# boxer_main.net
KiCad netlist of a schematic drawn in Altium Designer
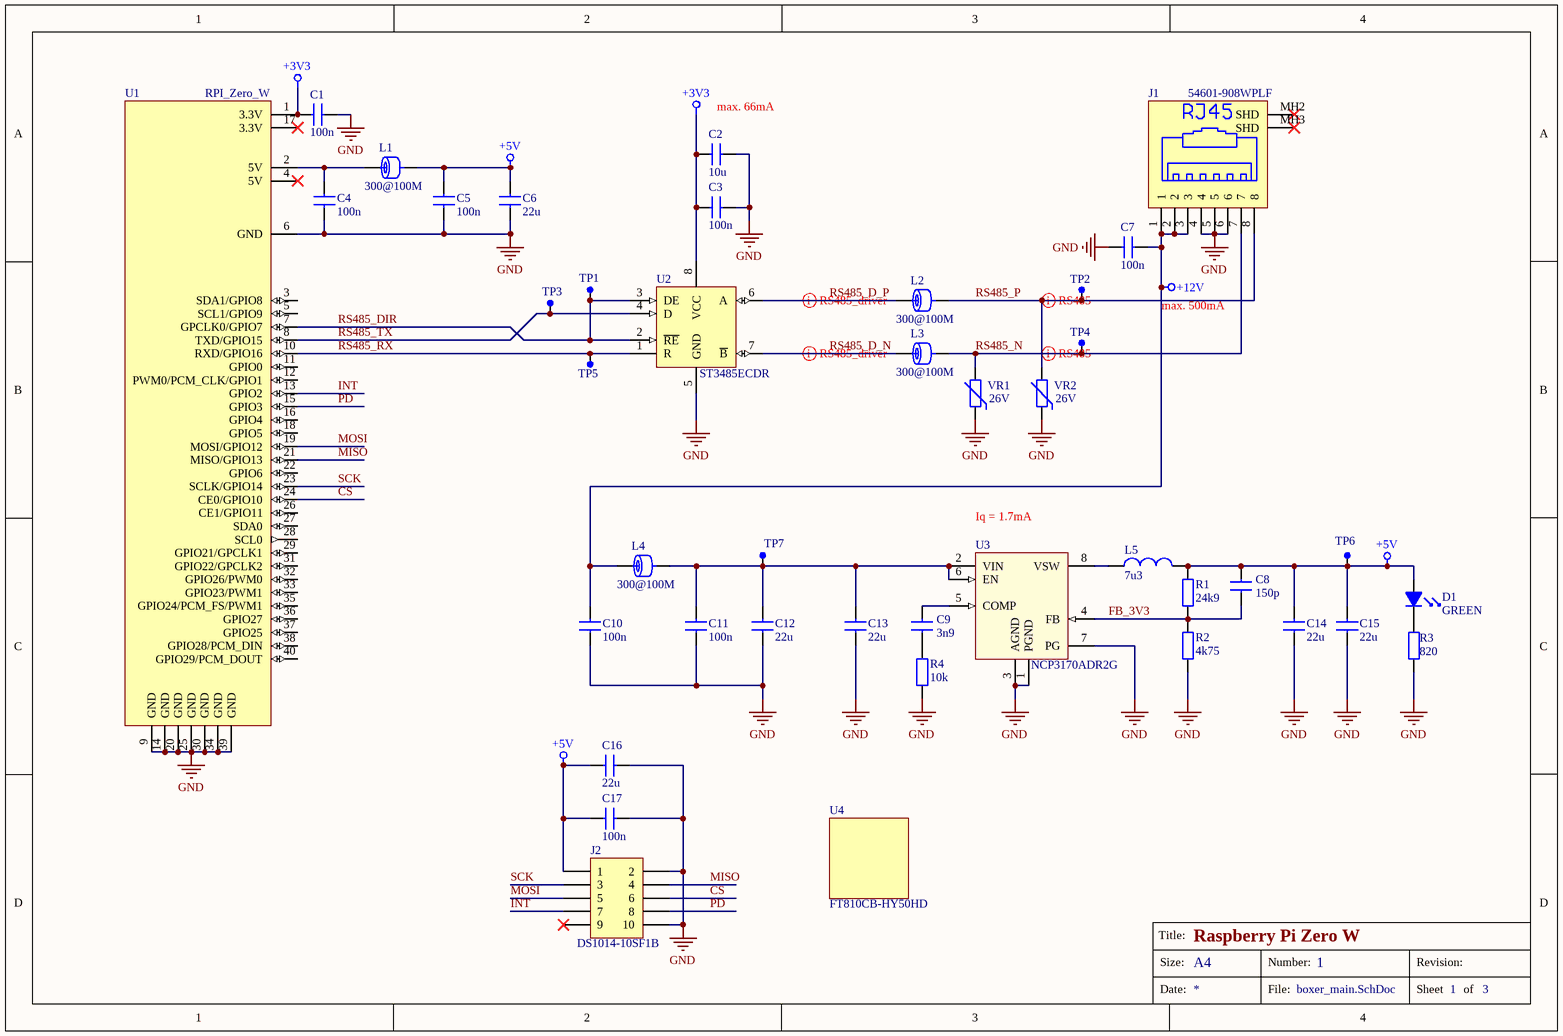
[diagram p0: boxer_main.SchDoc]

(export (version "E")
  (design (tool "Eeschema 10.0.6"))
  (components
    (comp (ref "C1")
      (value "100n")
      (footprint "C_0805")
      (description "Capacitor")
      (libsource (lib "boxer_pas") (part "Capacitor"))
    )
    (comp (ref "C2")
      (value "10u")
      (footprint "C_1206")
      (description "Capacitor")
      (fields (field (name "Comment") "TME: CL31A226MOCLNNC"))
      (libsource (lib "boxer_pas") (part "Capacitor"))
    )
    (comp (ref "C3")
      (value "100n")
      (footprint "C_0805")
      (description "Capacitor")
      (libsource (lib "boxer_pas") (part "Capacitor"))
    )
    (comp (ref "C4")
      (value "100n")
      (footprint "C_0805")
      (description "Capacitor")
      (libsource (lib "boxer_pas") (part "Capacitor"))
    )
    (comp (ref "C5")
      (value "100n")
      (footprint "C_0805")
      (description "Capacitor")
      (libsource (lib "boxer_pas") (part "Capacitor"))
    )
    (comp (ref "C6")
      (value "22u")
      (footprint "C_1206")
      (description "Capacitor")
      (fields (field (name "Comment") "TME: CL31A226MOCLNNC"))
      (libsource (lib "boxer_pas") (part "Capacitor"))
    )
    (comp (ref "C7")
      (value "100n")
      (footprint "C_0805")
      (description "Capacitor")
      (libsource (lib "boxer_pas") (part "Capacitor"))
    )
    (comp (ref "C8")
      (value "150p")
      (footprint "C_0805")
      (description "Capacitor")
      (fields (field (name "Comment") "885012207081"))
      (libsource (lib "boxer_pas") (part "Capacitor"))
    )
    (comp (ref "C9")
      (value "3n9")
      (footprint "C_0805")
      (description "Capacitor")
      (fields (field (name "Comment") "885012207089"))
      (libsource (lib "boxer_pas") (part "Capacitor"))
    )
    (comp (ref "C10")
      (value "100n")
      (footprint "C_0805")
      (description "Capacitor")
      (libsource (lib "boxer_pas") (part "Capacitor"))
    )
    (comp (ref "C11")
      (value "100n")
      (footprint "C_0805")
      (description "Capacitor")
      (libsource (lib "boxer_pas") (part "Capacitor"))
    )
    (comp (ref "C12")
      (value "22u")
      (footprint "C_1206")
      (description "Capacitor")
      (fields (field (name "Comment") "TME: CL31A226MOCLNNC"))
      (libsource (lib "boxer_pas") (part "Capacitor"))
    )
    (comp (ref "C13")
      (value "22u")
      (footprint "C_1206")
      (description "Capacitor")
      (fields (field (name "Comment") "TME: CL31A226MOCLNNC"))
      (libsource (lib "boxer_pas") (part "Capacitor"))
    )
    (comp (ref "C14")
      (value "22u")
      (footprint "C_1206")
      (description "Capacitor")
      (fields (field (name "Comment") "TME: CL31A226MOCLNNC"))
      (libsource (lib "boxer_pas") (part "Capacitor"))
    )
    (comp (ref "C15")
      (value "22u")
      (footprint "C_1206")
      (description "Capacitor")
      (fields (field (name "Comment") "TME: CL31A226MOCLNNC"))
      (libsource (lib "boxer_pas") (part "Capacitor"))
    )
    (comp (ref "C16")
      (value "22u")
      (footprint "C_1206")
      (description "Capacitor")
      (fields (field (name "Comment") "TME: CL31A226MOCLNNC"))
      (libsource (lib "boxer_pas") (part "Capacitor"))
    )
    (comp (ref "C17")
      (value "100n")
      (footprint "C_0805")
      (description "Capacitor")
      (libsource (lib "boxer_pas") (part "Capacitor"))
    )
    (comp (ref "D1")
      (value "GREEN")
      (footprint "LED_0805")
      (description "Typical RED, GREEN, YELLOW, AMBER GaAs LED")
      (fields (field (name "Comment") "KP-2012LSGC"))
      (libsource (lib "altium-import") (part "root_3_LED_"))
    )
    (comp (ref "J1")
      (value "54601-908WPLF")
      (footprint "RJ45_54601-908WPLF")
      (description "RJ45 Socket, 8pin, No Key, Molex MX-95001-2881")
      (libsource (lib "boxer_mechanical") (part "RJ45-8"))
    )
    (comp (ref "J2")
      (value "DS1014-10SF1B")
      (footprint "215307-5")
      (description "Header, 5-Pin, Dual row")
      (fields (field (name "Comment") "Header 5X2"))
      (libsource (lib "boxer_mechanical") (part "Header 5X2"))
    )
    (comp (ref "L1")
      (value "300@100M")
      (footprint "L_0805")
      (description "Ferrite Bead")
      (fields (field (name "Comment") "742792031"))
      (libsource (lib "boxer_pas") (part "FB"))
    )
    (comp (ref "L2")
      (value "300@100M")
      (footprint "L_0805")
      (description "Ferrite Bead")
      (fields (field (name "Comment") "742792031"))
      (libsource (lib "boxer_pas") (part "FB"))
    )
    (comp (ref "L3")
      (value "300@100M")
      (footprint "L_0805")
      (description "Ferrite Bead")
      (fields (field (name "Comment") "742792031"))
      (libsource (lib "boxer_pas") (part "FB"))
    )
    (comp (ref "L4")
      (value "300@100M")
      (footprint "L_0805")
      (description "Ferrite Bead")
      (fields (field (name "Comment") "742792031"))
      (libsource (lib "boxer_pas") (part "FB"))
    )
    (comp (ref "L5")
      (value "7u3")
      (footprint "L_6.7x6.7mm")
      (description "FIXED IND 7.3UH 2.1A 54 MOHM SMD")
      (fields (field (name "Comment") "308-1500-1-ND"))
      (libsource (lib "boxer_pas") (part "Inductor"))
    )
    (comp (ref "R1")
      (value "24k9")
      (footprint "R_0805")
      (description "Resistor")
      (fields (field (name "Comment") "RNCP0805FTD24K9"))
      (libsource (lib "boxer_pas") (part "Resistor"))
    )
    (comp (ref "R2")
      (value "4k75")
      (footprint "R_0805")
      (description "Resistor")
      (fields (field (name "Comment") "RNCP0805FTD4K75"))
      (libsource (lib "boxer_pas") (part "Resistor"))
    )
    (comp (ref "R3")
      (value "820")
      (footprint "R_0805")
      (description "Resistor")
      (libsource (lib "altium-import") (part "root_1_Resistor_"))
    )
    (comp (ref "R4")
      (value "10k")
      (footprint "R_1206")
      (description "Resistor")
      (libsource (lib "boxer_pas") (part "Resistor"))
    )
    (comp (ref "TP1")
      (value "TEST PAD")
      (footprint "PIN")
      (description "PAD 1.5mm")
      (libsource (lib "boxer_mechanical") (part "TEST_PAD"))
    )
    (comp (ref "TP2")
      (value "TEST PAD")
      (footprint "PIN")
      (description "PAD 1.5mm")
      (libsource (lib "boxer_mechanical") (part "TEST_PAD"))
    )
    (comp (ref "TP3")
      (value "TEST PAD")
      (footprint "PIN")
      (description "PAD 1.5mm")
      (libsource (lib "boxer_mechanical") (part "TEST_PAD"))
    )
    (comp (ref "TP4")
      (value "TEST PAD")
      (footprint "PIN")
      (description "PAD 1.5mm")
      (libsource (lib "boxer_mechanical") (part "TEST_PAD"))
    )
    (comp (ref "TP5")
      (value "TEST PAD")
      (footprint "PIN")
      (description "PAD 1.5mm")
      (libsource (lib "boxer_mechanical") (part "TEST_PAD"))
    )
    (comp (ref "TP6")
      (value "TEST PAD")
      (footprint "PIN")
      (description "PAD 1.5mm")
      (libsource (lib "boxer_mechanical") (part "TEST_PAD"))
    )
    (comp (ref "TP7")
      (value "TEST PAD")
      (footprint "PIN")
      (description "PAD 1.5mm")
      (libsource (lib "boxer_mechanical") (part "TEST_PAD"))
    )
    (comp (ref "U1")
      (value "RPI_Zero_W")
      (footprint "RPI_ZERO")
      (description "Raspberry Pi Zero W")
      (libsource (lib "boxer_ic") (part "RPI_Zero_W"))
    )
    (comp (ref "U2")
      (value "ST3485ECDR")
      (footprint "SO8")
      (description "RS-422/RS-485 Interface IC Hi-Spd Lo Pwr Trans")
      (libsource (lib "boxer_ic") (part "ST485BDR"))
    )
    (comp (ref "U3")
      (value "NCP3170ADR2G")
      (footprint "SO8")
      (description "Synchronous PWM Switching Converter")
      (libsource (lib "boxer_ic") (part "NCP3170"))
    )
    (comp (ref "U4")
      (value "FT810CB-HY50HD")
      (footprint "FT810CB-HY50HD")
      (libsource (lib "boxer_ic") (part "FT810CB-HY50HD"))
    )
    (comp (ref "VR1")
      (value "26V")
      (footprint "VR_0805")
      (description "34.5V 20A Varistor 1 Circuit Surface Mount, MLCV 0805 (2012 Metric)")
      (fields (field (name "Comment") "AMCV-0805-260-C800N-T"))
      (libsource (lib "boxer_pas") (part "Varistor"))
    )
    (comp (ref "VR2")
      (value "26V")
      (footprint "VR_0805")
      (description "34.5V 20A Varistor 1 Circuit Surface Mount, MLCV 0805 (2012 Metric)")
      (fields (field (name "Comment") "AMCV-0805-260-C800N-T"))
      (libsource (lib "boxer_pas") (part "Varistor"))
    )
  )
  (nets
    (net (code "1") (name "+3V3") (class "Default")
      (node (ref "C1") (pin "2") (pinfunction "2_2") (pintype "passive"))
      (node (ref "C2") (pin "2") (pinfunction "2_2") (pintype "passive"))
      (node (ref "C3") (pin "1") (pinfunction "1_1") (pintype "passive"))
      (node (ref "U1") (pin "1") (pinfunction "3.3V_1") (pintype "power_in"))
      (node (ref "U2") (pin "8") (pinfunction "VCC_8") (pintype "power_in"))
    )
    (net (code "2") (name "+5V") (class "Default")
      (node (ref "C14") (pin "2") (pinfunction "2_2") (pintype "passive"))
      (node (ref "C15") (pin "2") (pinfunction "2_2") (pintype "passive"))
      (node (ref "C16") (pin "2") (pinfunction "2_2") (pintype "passive"))
      (node (ref "C17") (pin "2") (pinfunction "2_2") (pintype "passive"))
      (node (ref "C5") (pin "1") (pinfunction "1_1") (pintype "passive"))
      (node (ref "C6") (pin "2") (pinfunction "2_2") (pintype "passive"))
      (node (ref "C8") (pin "2") (pinfunction "2_2") (pintype "passive"))
      (node (ref "D1") (pin "1") (pinfunction "A_1") (pintype "passive"))
      (node (ref "J2") (pin "1") (pinfunction "1_1") (pintype "passive"))
      (node (ref "L1") (pin "2") (pinfunction "2_2") (pintype "passive"))
      (node (ref "L5") (pin "2") (pinfunction "2_2") (pintype "passive"))
      (node (ref "R1") (pin "2") (pinfunction "2_2") (pintype "passive"))
      (node (ref "TP6") (pin "1") (pinfunction "1_1") (pintype "passive"))
    )
    (net (code "3") (name "+12V") (class "Default")
      (node (ref "C10") (pin "2") (pinfunction "2_2") (pintype "passive"))
      (node (ref "C7") (pin "1") (pinfunction "1_1") (pintype "passive"))
      (node (ref "J1") (pin "1") (pinfunction "1_1") (pintype "passive"))
      (node (ref "J1") (pin "2") (pinfunction "2_2") (pintype "passive"))
      (node (ref "J1") (pin "3") (pinfunction "3_3") (pintype "passive"))
      (node (ref "L4") (pin "1") (pinfunction "1_1") (pintype "passive"))
    )
    (net (code "4") (name "/CS") (class "Default")
      (node (ref "J2") (pin "6") (pinfunction "6_6") (pintype "passive"))
      (node (ref "U1") (pin "24") (pinfunction "CE0/GPIO10_24") (pintype "bidirectional"))
    )
    (net (code "5") (name "/FB_3V3") (class "Default")
      (node (ref "C8") (pin "1") (pinfunction "1_1") (pintype "passive"))
      (node (ref "R1") (pin "1") (pinfunction "1_1") (pintype "passive"))
      (node (ref "R2") (pin "2") (pinfunction "2_2") (pintype "passive"))
      (node (ref "U3") (pin "4") (pinfunction "FB_4") (pintype "input"))
    )
    (net (code "6") (name "/INT") (class "Default")
      (node (ref "J2") (pin "7") (pinfunction "7_7") (pintype "passive"))
      (node (ref "U1") (pin "13") (pinfunction "GPIO2_13") (pintype "bidirectional"))
    )
    (net (code "7") (name "/MISO") (class "Default")
      (node (ref "J2") (pin "4") (pinfunction "4_4") (pintype "passive"))
      (node (ref "U1") (pin "21") (pinfunction "MISO/GPIO13_21") (pintype "bidirectional"))
    )
    (net (code "8") (name "/MOSI") (class "Default")
      (node (ref "J2") (pin "5") (pinfunction "5_5") (pintype "passive"))
      (node (ref "U1") (pin "19") (pinfunction "MOSI/GPIO12_19") (pintype "bidirectional"))
    )
    (net (code "9") (name "/PD") (class "Default")
      (node (ref "J2") (pin "8") (pinfunction "8_8") (pintype "passive"))
      (node (ref "U1") (pin "15") (pinfunction "GPIO3_15") (pintype "bidirectional"))
    )
    (net (code "10") (name "/RS485_DIR") (class "Default")
      (node (ref "TP1") (pin "1") (pinfunction "1_1") (pintype "passive"))
      (node (ref "U1") (pin "7") (pinfunction "GPCLK0/GPIO7_7") (pintype "bidirectional"))
      (node (ref "U2") (pin "2") (pinfunction "~{RE}_2") (pintype "input"))
      (node (ref "U2") (pin "3") (pinfunction "DE_3") (pintype "input"))
    )
    (net (code "11") (name "/RS485_D_N") (class "Default")
      (node (ref "L3") (pin "1") (pinfunction "1_1") (pintype "passive"))
      (node (ref "U2") (pin "7") (pinfunction "~{B}_7") (pintype "bidirectional"))
    )
    (net (code "12") (name "/RS485_D_P") (class "Default")
      (node (ref "L2") (pin "1") (pinfunction "1_1") (pintype "passive"))
      (node (ref "U2") (pin "6") (pinfunction "A_6") (pintype "bidirectional"))
    )
    (net (code "13") (name "/RS485_N") (class "Default")
      (node (ref "J1") (pin "7") (pinfunction "7_7") (pintype "passive"))
      (node (ref "L3") (pin "2") (pinfunction "2_2") (pintype "passive"))
      (node (ref "TP4") (pin "1") (pinfunction "1_1") (pintype "passive"))
      (node (ref "VR1") (pin "1") (pinfunction "1_1") (pintype "passive"))
    )
    (net (code "14") (name "/RS485_P") (class "Default")
      (node (ref "J1") (pin "8") (pinfunction "8_8") (pintype "passive"))
      (node (ref "L2") (pin "2") (pinfunction "2_2") (pintype "passive"))
      (node (ref "TP2") (pin "1") (pinfunction "1_1") (pintype "passive"))
      (node (ref "VR2") (pin "1") (pinfunction "1_1") (pintype "passive"))
    )
    (net (code "15") (name "/RS485_RX") (class "Default")
      (node (ref "TP5") (pin "1") (pinfunction "1_1") (pintype "passive"))
      (node (ref "U1") (pin "10") (pinfunction "RXD/GPIO16_10") (pintype "bidirectional"))
      (node (ref "U2") (pin "1") (pinfunction "R_1") (pintype "tri_state"))
    )
    (net (code "16") (name "/RS485_TX") (class "Default")
      (node (ref "TP3") (pin "1") (pinfunction "1_1") (pintype "passive"))
      (node (ref "U1") (pin "8") (pinfunction "TXD/GPIO15_8") (pintype "bidirectional"))
      (node (ref "U2") (pin "4") (pinfunction "D_4") (pintype "input"))
    )
    (net (code "17") (name "/SCK") (class "Default")
      (node (ref "J2") (pin "3") (pinfunction "3_3") (pintype "passive"))
      (node (ref "U1") (pin "23") (pinfunction "SCLK/GPIO14_23") (pintype "bidirectional"))
    )
    (net (code "18") (name "GND") (class "Default")
      (node (ref "C1") (pin "1") (pinfunction "1_1") (pintype "passive"))
      (node (ref "C10") (pin "1") (pinfunction "1_1") (pintype "passive"))
      (node (ref "C11") (pin "1") (pinfunction "1_1") (pintype "passive"))
      (node (ref "C12") (pin "1") (pinfunction "1_1") (pintype "passive"))
      (node (ref "C13") (pin "1") (pinfunction "1_1") (pintype "passive"))
      (node (ref "C14") (pin "1") (pinfunction "1_1") (pintype "passive"))
      (node (ref "C15") (pin "1") (pinfunction "1_1") (pintype "passive"))
      (node (ref "C16") (pin "1") (pinfunction "1_1") (pintype "passive"))
      (node (ref "C17") (pin "1") (pinfunction "1_1") (pintype "passive"))
      (node (ref "C2") (pin "1") (pinfunction "1_1") (pintype "passive"))
      (node (ref "C3") (pin "2") (pinfunction "2_2") (pintype "passive"))
      (node (ref "C4") (pin "2") (pinfunction "2_2") (pintype "passive"))
      (node (ref "C5") (pin "2") (pinfunction "2_2") (pintype "passive"))
      (node (ref "C6") (pin "1") (pinfunction "1_1") (pintype "passive"))
      (node (ref "C7") (pin "2") (pinfunction "2_2") (pintype "passive"))
      (node (ref "J1") (pin "4") (pinfunction "4_4") (pintype "passive"))
      (node (ref "J1") (pin "5") (pinfunction "5_5") (pintype "passive"))
      (node (ref "J1") (pin "6") (pinfunction "6_6") (pintype "passive"))
      (node (ref "J2") (pin "10") (pinfunction "10_10") (pintype "passive"))
      (node (ref "J2") (pin "2") (pinfunction "2_2") (pintype "passive"))
      (node (ref "R2") (pin "1") (pinfunction "1_1") (pintype "passive"))
      (node (ref "R3") (pin "1") (pinfunction "1_1") (pintype "passive"))
      (node (ref "R4") (pin "1") (pinfunction "1_1") (pintype "passive"))
      (node (ref "U1") (pin "14") (pinfunction "GND_14") (pintype "power_in"))
      (node (ref "U1") (pin "20") (pinfunction "GND_20") (pintype "power_in"))
      (node (ref "U1") (pin "25") (pinfunction "GND_25") (pintype "power_in"))
      (node (ref "U1") (pin "30") (pinfunction "GND_30") (pintype "power_in"))
      (node (ref "U1") (pin "34") (pinfunction "GND_34") (pintype "power_in"))
      (node (ref "U1") (pin "39") (pinfunction "GND_39") (pintype "power_in"))
      (node (ref "U1") (pin "6") (pinfunction "GND_6") (pintype "power_in"))
      (node (ref "U1") (pin "9") (pinfunction "GND_9") (pintype "power_in"))
      (node (ref "U2") (pin "5") (pinfunction "GND_5") (pintype "power_in"))
      (node (ref "U3") (pin "1") (pinfunction "PGND_1") (pintype "power_in"))
      (node (ref "U3") (pin "3") (pinfunction "AGND_3") (pintype "power_in"))
      (node (ref "U3") (pin "7") (pinfunction "PG_7") (pintype "passive"))
      (node (ref "VR1") (pin "2") (pinfunction "2_2") (pintype "passive"))
      (node (ref "VR2") (pin "2") (pinfunction "2_2") (pintype "passive"))
    )
    (net (code "19") (name "Net-(C4-Pad1)") (class "Default")
      (node (ref "C4") (pin "1") (pinfunction "1_1") (pintype "passive"))
      (node (ref "L1") (pin "1") (pinfunction "1_1") (pintype "passive"))
      (node (ref "U1") (pin "2") (pinfunction "5V_2") (pintype "power_in"))
    )
    (net (code "20") (name "Net-(C9-Pad1)") (class "Default")
      (node (ref "C9") (pin "1") (pinfunction "1_1") (pintype "passive"))
      (node (ref "R4") (pin "2") (pinfunction "2_2") (pintype "passive"))
    )
    (net (code "21") (name "Net-(D1-K)") (class "Default")
      (node (ref "D1") (pin "2") (pinfunction "K_2") (pintype "passive"))
      (node (ref "R3") (pin "2") (pinfunction "2_2") (pintype "passive"))
    )
    (net (code "22") (name "Net-(U3-COMP)") (class "Default")
      (node (ref "C9") (pin "2") (pinfunction "2_2") (pintype "passive"))
      (node (ref "U3") (pin "5") (pinfunction "COMP_5") (pintype "input"))
    )
    (net (code "23") (name "Net-(U3-EN)") (class "Default")
      (node (ref "C11") (pin "2") (pinfunction "2_2") (pintype "passive"))
      (node (ref "C12") (pin "2") (pinfunction "2_2") (pintype "passive"))
      (node (ref "C13") (pin "2") (pinfunction "2_2") (pintype "passive"))
      (node (ref "L4") (pin "2") (pinfunction "2_2") (pintype "passive"))
      (node (ref "TP7") (pin "1") (pinfunction "1_1") (pintype "passive"))
      (node (ref "U3") (pin "2") (pinfunction "VIN_2") (pintype "power_in"))
      (node (ref "U3") (pin "6") (pinfunction "EN_6") (pintype "input"))
    )
    (net (code "24") (name "Net-(U3-VSW)") (class "Default")
      (node (ref "L5") (pin "1") (pinfunction "1_1") (pintype "passive"))
      (node (ref "U3") (pin "8") (pinfunction "VSW_8") (pintype "power_in"))
    )
    (net (code "25") (name "unconnected-(J1-SHD-PadMH2)") (class "Default")
      (node (ref "J1") (pin "MH2") (pinfunction "SHD_MH2") (pintype "passive+no_connect"))
    )
    (net (code "26") (name "unconnected-(J1-SHD-PadMH3)") (class "Default")
      (node (ref "J1") (pin "MH3") (pinfunction "SHD_MH3") (pintype "passive+no_connect"))
    )
    (net (code "27") (name "unconnected-(J2-Pad9)") (class "Default")
      (node (ref "J2") (pin "9") (pinfunction "9_9") (pintype "passive+no_connect"))
    )
    (net (code "28") (name "unconnected-(U1-3.3V-Pad17)") (class "Default")
      (node (ref "U1") (pin "17") (pinfunction "3.3V_17") (pintype "power_in+no_connect"))
    )
    (net (code "29") (name "unconnected-(U1-5V-Pad4)") (class "Default")
      (node (ref "U1") (pin "4") (pinfunction "5V_4") (pintype "power_in+no_connect"))
    )
    (net (code "30") (name "unconnected-(U1-CE1{slash}GPIO11-Pad26)") (class "Default")
      (node (ref "U1") (pin "26") (pinfunction "CE1/GPIO11_26") (pintype "bidirectional"))
    )
    (net (code "31") (name "unconnected-(U1-GPIO0-Pad11)") (class "Default")
      (node (ref "U1") (pin "11") (pinfunction "GPIO0_11") (pintype "bidirectional"))
    )
    (net (code "32") (name "unconnected-(U1-GPIO4-Pad16)") (class "Default")
      (node (ref "U1") (pin "16") (pinfunction "GPIO4_16") (pintype "bidirectional"))
    )
    (net (code "33") (name "unconnected-(U1-GPIO5-Pad18)") (class "Default")
      (node (ref "U1") (pin "18") (pinfunction "GPIO5_18") (pintype "bidirectional"))
    )
    (net (code "34") (name "unconnected-(U1-GPIO6-Pad22)") (class "Default")
      (node (ref "U1") (pin "22") (pinfunction "GPIO6_22") (pintype "bidirectional"))
    )
    (net (code "35") (name "unconnected-(U1-GPIO21{slash}GPCLK1-Pad29)") (class "Default")
      (node (ref "U1") (pin "29") (pinfunction "GPIO21/GPCLK1_29") (pintype "bidirectional"))
    )
    (net (code "36") (name "unconnected-(U1-GPIO22{slash}GPCLK2-Pad31)") (class "Default")
      (node (ref "U1") (pin "31") (pinfunction "GPIO22/GPCLK2_31") (pintype "bidirectional"))
    )
    (net (code "37") (name "unconnected-(U1-GPIO23{slash}PWM1-Pad33)") (class "Default")
      (node (ref "U1") (pin "33") (pinfunction "GPIO23/PWM1_33") (pintype "bidirectional"))
    )
    (net (code "38") (name "unconnected-(U1-GPIO24{slash}PCM_FS{slash}PWM1-Pad35)") (class "Default")
      (node (ref "U1") (pin "35") (pinfunction "GPIO24/PCM_FS/PWM1_35") (pintype "bidirectional"))
    )
    (net (code "39") (name "unconnected-(U1-GPIO25-Pad37)") (class "Default")
      (node (ref "U1") (pin "37") (pinfunction "GPIO25_37") (pintype "bidirectional"))
    )
    (net (code "40") (name "unconnected-(U1-GPIO26{slash}PWM0-Pad32)") (class "Default")
      (node (ref "U1") (pin "32") (pinfunction "GPIO26/PWM0_32") (pintype "bidirectional"))
    )
    (net (code "41") (name "unconnected-(U1-GPIO27-Pad36)") (class "Default")
      (node (ref "U1") (pin "36") (pinfunction "GPIO27_36") (pintype "bidirectional"))
    )
    (net (code "42") (name "unconnected-(U1-GPIO28{slash}PCM_DIN-Pad38)") (class "Default")
      (node (ref "U1") (pin "38") (pinfunction "GPIO28/PCM_DIN_38") (pintype "bidirectional"))
    )
    (net (code "43") (name "unconnected-(U1-GPIO29{slash}PCM_DOUT-Pad40)") (class "Default")
      (node (ref "U1") (pin "40") (pinfunction "GPIO29/PCM_DOUT_40") (pintype "bidirectional"))
    )
    (net (code "44") (name "unconnected-(U1-PWM0{slash}PCM_CLK{slash}GPIO1-Pad12)") (class "Default")
      (node (ref "U1") (pin "12") (pinfunction "PWM0/PCM_CLK/GPIO1_12") (pintype "bidirectional"))
    )
    (net (code "45") (name "unconnected-(U1-SCL0-Pad28)") (class "Default")
      (node (ref "U1") (pin "28") (pinfunction "SCL0_28") (pintype "output"))
    )
    (net (code "46") (name "unconnected-(U1-SCL1{slash}GPIO9-Pad5)") (class "Default")
      (node (ref "U1") (pin "5") (pinfunction "SCL1/GPIO9_5") (pintype "bidirectional"))
    )
    (net (code "47") (name "unconnected-(U1-SDA0-Pad27)") (class "Default")
      (node (ref "U1") (pin "27") (pinfunction "SDA0_27") (pintype "bidirectional"))
    )
    (net (code "48") (name "unconnected-(U1-SDA1{slash}GPIO8-Pad3)") (class "Default")
      (node (ref "U1") (pin "3") (pinfunction "SDA1/GPIO8_3") (pintype "bidirectional"))
    )
  )
)
